# Kajtu_-DSP_eeprom.net
KiCad netlist of a schematic drawn in Altium Designer
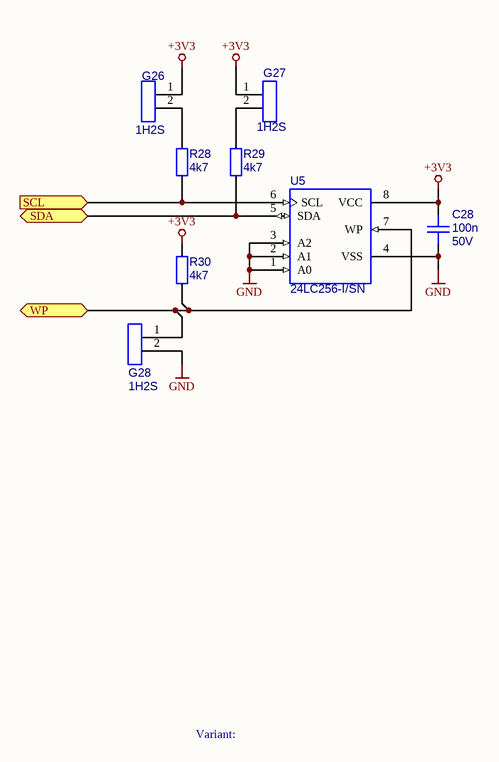
[diagram p0: Kajtuś-DSP_eeprom.SchDoc]

(export (version "E")
  (design (tool "Eeschema 10.0.6"))
  (components
    (comp (ref "C28")
      (value "100n")
      (footprint "C_0603_MA")
      (description "Kondensator ceramiczny SMD")
      (fields (field (name "PART NUMBER") "C_0603_100n_50V_X7R") (field (name "VOLTAGE") "50V"))
      (libsource (lib "AD_ostry_intlib") (part "C_0603_100n_50V_X7R"))
    )
    (comp (ref "G26")
      (value "1H2S")
      (footprint "1H2S_FHS")
      (description "Listwa jednorzędowa, 1x2 piny, raster 2,54mm")
      (fields (field (name "PART NUMBER") "G_1H2S") (field (name "MANUFACTURER") "generic"))
      (libsource (lib "") (part "G_1H2S_1"))
    )
    (comp (ref "G27")
      (value "1H2S")
      (footprint "1H2S_FHS")
      (description "Listwa jednorzędowa, 1x2 piny, raster 2,54mm")
      (fields (field (name "PART NUMBER") "G_1H2S") (field (name "MANUFACTURER") "generic"))
      (libsource (lib "AD_ostry_intlib") (part "G_1H2S"))
    )
    (comp (ref "G28")
      (value "1H2S")
      (footprint "1H2S_FHS")
      (description "Listwa jednorzędowa, 1x2 piny, raster 2,54mm")
      (fields (field (name "PART NUMBER") "G_1H2S") (field (name "MANUFACTURER") "generic"))
      (libsource (lib "") (part "G_1H2S_1"))
    )
    (comp (ref "R28")
      (value "4k7")
      (footprint "R_0603_MA")
      (description "Rezystor SMD")
      (fields (field (name "PART NUMBER") "R_0603_4k7_5%") (field (name "MANUFACTURER") "Royal Ohm"))
      (libsource (lib "AD_ostry_intlib") (part "R_0603_4k7_5%"))
    )
    (comp (ref "R29")
      (value "4k7")
      (footprint "R_0603_MA")
      (description "Rezystor SMD")
      (fields (field (name "PART NUMBER") "R_0603_4k7_5%") (field (name "MANUFACTURER") "Royal Ohm"))
      (libsource (lib "AD_ostry_intlib") (part "R_0603_4k7_5%"))
    )
    (comp (ref "R30")
      (value "4k7")
      (footprint "R_0603_MA")
      (description "Rezystor SMD")
      (fields (field (name "PART NUMBER") "R_0603_4k7_5%") (field (name "MANUFACTURER") "Royal Ohm"))
      (libsource (lib "AD_ostry_intlib") (part "R_0603_4k7_5%"))
    )
    (comp (ref "U5")
      (value "24LC256-I/SN")
      (footprint "SO-8")
      (description "256Kbit, 400kHz, 2.5V, I2C Serial EEPROM, 8-Pin SOIC 150mil, Industrial Temperature")
      (fields (field (name "MANUFACTURER") "Microchip"))
      (libsource (lib "AD_ostry_intlib") (part "U_24LC256-I/SN"))
    )
  )
  (nets
    (net (code "1") (name "+3V3") (class "Default")
      (node (ref "C28") (pin "1") (pinfunction "1_1") (pintype "passive"))
      (node (ref "G26") (pin "1") (pinfunction "1_1") (pintype "passive"))
      (node (ref "G27") (pin "1") (pinfunction "1_1") (pintype "passive"))
      (node (ref "R30") (pin "1") (pinfunction "1_1") (pintype "passive"))
      (node (ref "U5") (pin "8") (pinfunction "VCC_8") (pintype "power_in"))
    )
    (net (code "2") (name "/SCL") (class "Default")
      (node (ref "R28") (pin "2") (pinfunction "2_2") (pintype "passive"))
      (node (ref "U5") (pin "6") (pinfunction "SCL_6") (pintype "input"))
    )
    (net (code "3") (name "/SDA") (class "Default")
      (node (ref "R29") (pin "2") (pinfunction "2_2") (pintype "passive"))
      (node (ref "U5") (pin "5") (pinfunction "SDA_5") (pintype "bidirectional"))
    )
    (net (code "4") (name "/WP") (class "Default")
      (node (ref "G28") (pin "1") (pinfunction "1_1") (pintype "passive"))
      (node (ref "R30") (pin "2") (pinfunction "2_2") (pintype "passive"))
      (node (ref "U5") (pin "7") (pinfunction "WP_7") (pintype "input"))
    )
    (net (code "5") (name "GND") (class "Default")
      (node (ref "C28") (pin "2") (pinfunction "2_2") (pintype "passive"))
      (node (ref "G28") (pin "2") (pinfunction "2_2") (pintype "passive"))
      (node (ref "U5") (pin "1") (pinfunction "A0_1") (pintype "input"))
      (node (ref "U5") (pin "2") (pinfunction "A1_2") (pintype "input"))
      (node (ref "U5") (pin "3") (pinfunction "A2_3") (pintype "input"))
      (node (ref "U5") (pin "4") (pinfunction "VSS_4") (pintype "power_in"))
    )
    (net (code "6") (name "Net-(G26-Pad2)") (class "Default")
      (node (ref "G26") (pin "2") (pinfunction "2_2") (pintype "passive"))
      (node (ref "R28") (pin "1") (pinfunction "1_1") (pintype "passive"))
    )
    (net (code "7") (name "Net-(G27-Pad2)") (class "Default")
      (node (ref "G27") (pin "2") (pinfunction "2_2") (pintype "passive"))
      (node (ref "R29") (pin "1") (pinfunction "1_1") (pintype "passive"))
    )
  )
)
